# ZYNQ_BANK.net
KiCad netlist of a schematic drawn in Altium Designer
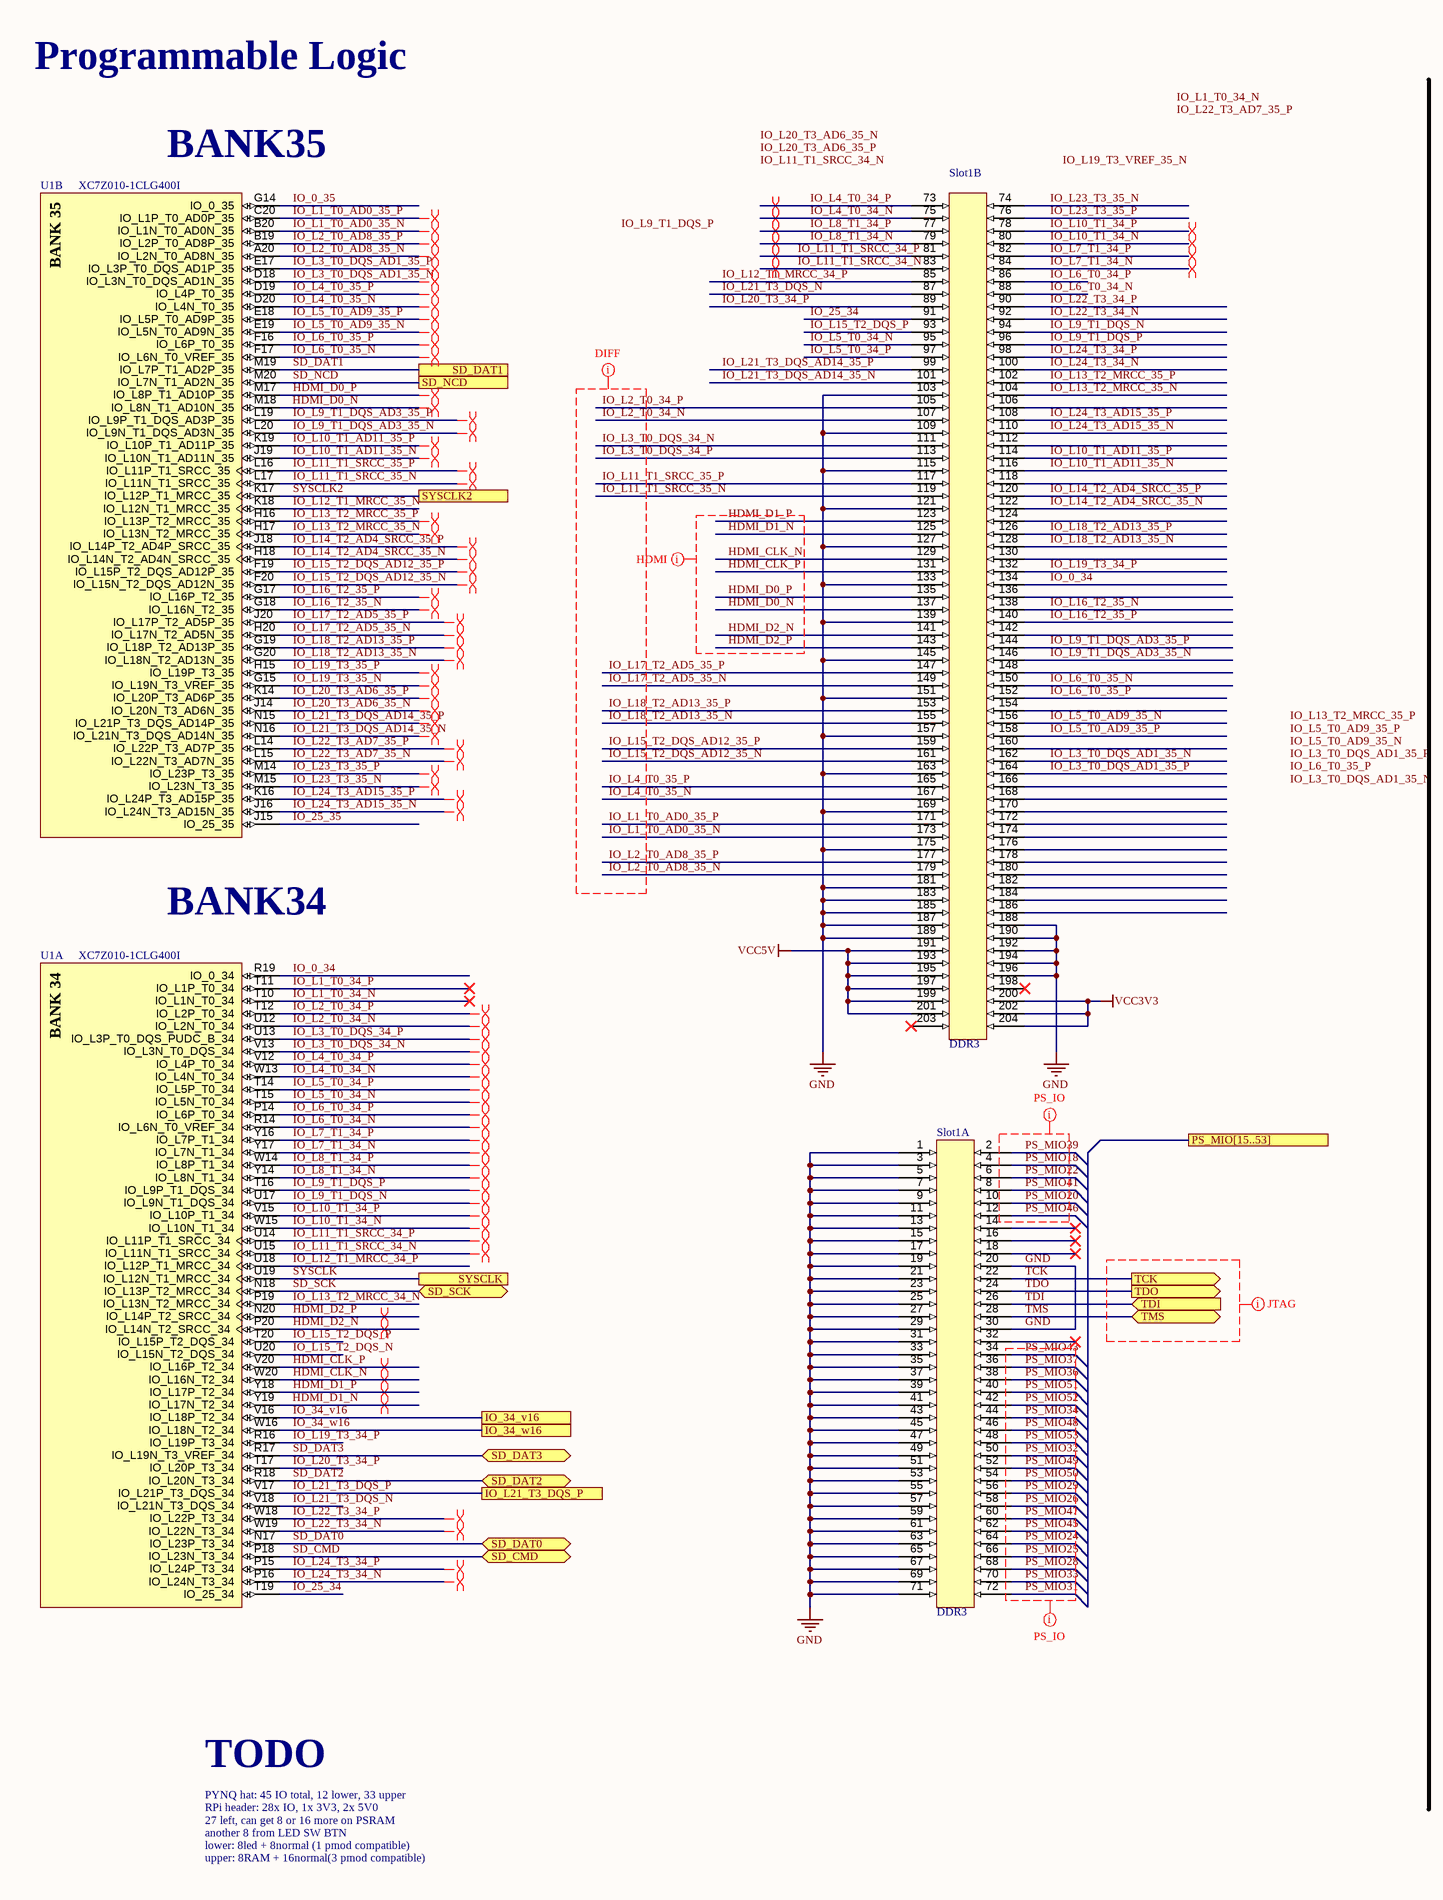
[diagram p0: ZYNQ_BANK.SchDoc, left]
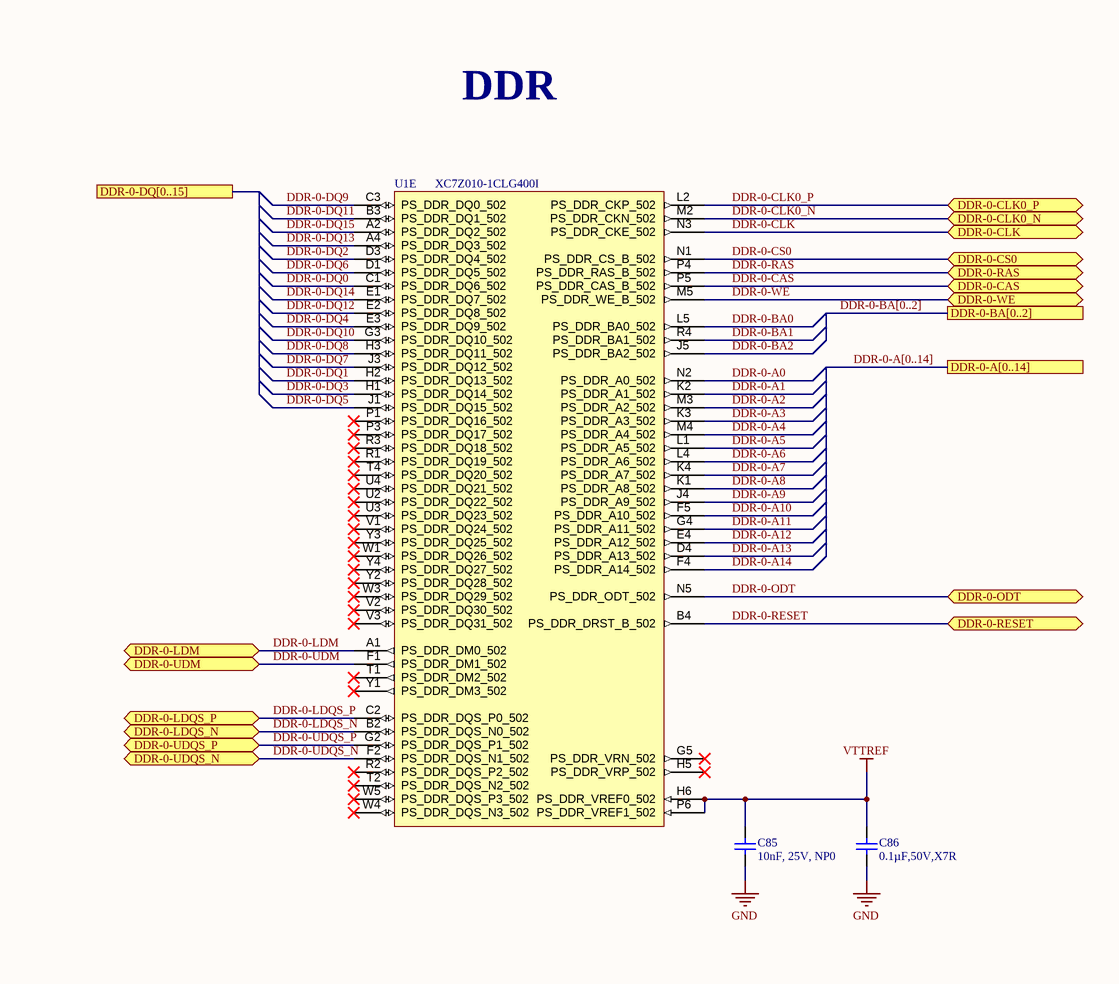
[diagram p1: ZYNQ_BANK.SchDoc, right]

(export (version "E")
  (design (tool "Eeschema 10.0.6"))
  (components
    (comp (ref "C85")
      (value "10nF, 25V, NP0")
      (footprint "CAP0402i")
      (description "0402,10nF,5%,25V,NP0")
      (fields (field (name "PART NUMBER") "GRM1555C1E103JE01J") (field (name "MANUFACTURER") "Murata"))
      (libsource (lib "AmpherLib") (part "Cap_10nF_25V_NP0_0402"))
    )
    (comp (ref "C86")
      (value "0.1µF,50V,X7R")
      (footprint "CAP0402i")
      (description "0402, 0.1uF, 10%,  50V, X7R")
      (fields (field (name "PART NUMBER") "C1005X7R1H104K050BE") (field (name "VOLTAGE") "50V"))
      (libsource (lib "AmpherLib") (part "Cap_0.1uF_50V_X7R_0402"))
    )
    (comp (ref "Slot1")
      (value "DDR3")
      (footprint "SODIMM_DDR3_EDGE")
      (libsource (lib "AmpherLib") (part "Slot_DDR3"))
    )
    (comp (ref "U1")
      (value "XC7Z010-1CLG400I")
      (footprint "CLG400")
      (fields (field (name "GENERIC PART NUMBER") "XC7Z010") (field (name "MANUFACTURER") "Xilinx"))
      (libsource (lib "CCZynq") (part "XC7Z010-1CLG400I"))
    )
  )
  (nets
    (net (code "14") (name "/DDR-0-A0") (class "Default")
      (node (ref "U1") (pin "N2") (pinfunction "PS_DDR_A0_502_N2") (pintype "output"))
    )
    (net (code "15") (name "/DDR-0-A1") (class "Default")
      (node (ref "U1") (pin "K2") (pinfunction "PS_DDR_A1_502_K2") (pintype "output"))
    )
    (net (code "16") (name "/DDR-0-A2") (class "Default")
      (node (ref "U1") (pin "M3") (pinfunction "PS_DDR_A2_502_M3") (pintype "output"))
    )
    (net (code "17") (name "/DDR-0-A3") (class "Default")
      (node (ref "U1") (pin "K3") (pinfunction "PS_DDR_A3_502_K3") (pintype "output"))
    )
    (net (code "18") (name "/DDR-0-A4") (class "Default")
      (node (ref "U1") (pin "M4") (pinfunction "PS_DDR_A4_502_M4") (pintype "output"))
    )
    (net (code "19") (name "/DDR-0-A5") (class "Default")
      (node (ref "U1") (pin "L1") (pinfunction "PS_DDR_A5_502_L1") (pintype "output"))
    )
    (net (code "20") (name "/DDR-0-A6") (class "Default")
      (node (ref "U1") (pin "L4") (pinfunction "PS_DDR_A6_502_L4") (pintype "output"))
    )
    (net (code "21") (name "/DDR-0-A7") (class "Default")
      (node (ref "U1") (pin "K4") (pinfunction "PS_DDR_A7_502_K4") (pintype "output"))
    )
    (net (code "22") (name "/DDR-0-A8") (class "Default")
      (node (ref "U1") (pin "K1") (pinfunction "PS_DDR_A8_502_K1") (pintype "output"))
    )
    (net (code "23") (name "/DDR-0-A9") (class "Default")
      (node (ref "U1") (pin "J4") (pinfunction "PS_DDR_A9_502_J4") (pintype "output"))
    )
    (net (code "24") (name "/DDR-0-A10") (class "Default")
      (node (ref "U1") (pin "F5") (pinfunction "PS_DDR_A10_502_F5") (pintype "output"))
    )
    (net (code "25") (name "/DDR-0-A11") (class "Default")
      (node (ref "U1") (pin "G4") (pinfunction "PS_DDR_A11_502_G4") (pintype "output"))
    )
    (net (code "26") (name "/DDR-0-A12") (class "Default")
      (node (ref "U1") (pin "E4") (pinfunction "PS_DDR_A12_502_E4") (pintype "output"))
    )
    (net (code "27") (name "/DDR-0-A13") (class "Default")
      (node (ref "U1") (pin "D4") (pinfunction "PS_DDR_A13_502_D4") (pintype "output"))
    )
    (net (code "28") (name "/DDR-0-A14") (class "Default")
      (node (ref "U1") (pin "F4") (pinfunction "PS_DDR_A14_502_F4") (pintype "output"))
    )
    (net (code "30") (name "/DDR-0-BA0") (class "Default")
      (node (ref "U1") (pin "L5") (pinfunction "PS_DDR_BA0_502_L5") (pintype "output"))
    )
    (net (code "31") (name "/DDR-0-BA1") (class "Default")
      (node (ref "U1") (pin "R4") (pinfunction "PS_DDR_BA1_502_R4") (pintype "output"))
    )
    (net (code "32") (name "/DDR-0-BA2") (class "Default")
      (node (ref "U1") (pin "J5") (pinfunction "PS_DDR_BA2_502_J5") (pintype "output"))
    )
    (net (code "34") (name "/DDR-0-CAS") (class "Default")
      (node (ref "U1") (pin "P5") (pinfunction "PS_DDR_CAS_B_502_P5") (pintype "output"))
    )
    (net (code "35") (name "/DDR-0-CLK") (class "Default")
      (node (ref "U1") (pin "N3") (pinfunction "PS_DDR_CKE_502_N3") (pintype "output"))
    )
    (net (code "36") (name "/DDR-0-CLK0_N") (class "Default")
      (node (ref "U1") (pin "M2") (pinfunction "PS_DDR_CKN_502_M2") (pintype "output"))
    )
    (net (code "37") (name "/DDR-0-CLK0_P") (class "Default")
      (node (ref "U1") (pin "L2") (pinfunction "PS_DDR_CKP_502_L2") (pintype "output"))
    )
    (net (code "38") (name "/DDR-0-CS0") (class "Default")
      (node (ref "U1") (pin "N1") (pinfunction "PS_DDR_CS_B_502_N1") (pintype "output"))
    )
    (net (code "39") (name "/DDR-0-DQ0") (class "Default")
      (node (ref "U1") (pin "C1") (pinfunction "PS_DDR_DQ6_502_C1") (pintype "bidirectional"))
    )
    (net (code "40") (name "/DDR-0-DQ1") (class "Default")
      (node (ref "U1") (pin "H2") (pinfunction "PS_DDR_DQ13_502_H2") (pintype "bidirectional"))
    )
    (net (code "41") (name "/DDR-0-DQ2") (class "Default")
      (node (ref "U1") (pin "D3") (pinfunction "PS_DDR_DQ4_502_D3") (pintype "bidirectional"))
    )
    (net (code "42") (name "/DDR-0-DQ3") (class "Default")
      (node (ref "U1") (pin "H1") (pinfunction "PS_DDR_DQ14_502_H1") (pintype "bidirectional"))
    )
    (net (code "43") (name "/DDR-0-DQ4") (class "Default")
      (node (ref "U1") (pin "E3") (pinfunction "PS_DDR_DQ9_502_E3") (pintype "bidirectional"))
    )
    (net (code "44") (name "/DDR-0-DQ5") (class "Default")
      (node (ref "U1") (pin "J1") (pinfunction "PS_DDR_DQ15_502_J1") (pintype "bidirectional"))
    )
    (net (code "45") (name "/DDR-0-DQ6") (class "Default")
      (node (ref "U1") (pin "D1") (pinfunction "PS_DDR_DQ5_502_D1") (pintype "bidirectional"))
    )
    (net (code "46") (name "/DDR-0-DQ7") (class "Default")
      (node (ref "U1") (pin "J3") (pinfunction "PS_DDR_DQ12_502_J3") (pintype "bidirectional"))
    )
    (net (code "47") (name "/DDR-0-DQ8") (class "Default")
      (node (ref "U1") (pin "H3") (pinfunction "PS_DDR_DQ11_502_H3") (pintype "bidirectional"))
    )
    (net (code "48") (name "/DDR-0-DQ9") (class "Default")
      (node (ref "U1") (pin "C3") (pinfunction "PS_DDR_DQ0_502_C3") (pintype "bidirectional"))
    )
    (net (code "49") (name "/DDR-0-DQ10") (class "Default")
      (node (ref "U1") (pin "G3") (pinfunction "PS_DDR_DQ10_502_G3") (pintype "bidirectional"))
    )
    (net (code "50") (name "/DDR-0-DQ11") (class "Default")
      (node (ref "U1") (pin "B3") (pinfunction "PS_DDR_DQ1_502_B3") (pintype "bidirectional"))
    )
    (net (code "51") (name "/DDR-0-DQ12") (class "Default")
      (node (ref "U1") (pin "E2") (pinfunction "PS_DDR_DQ8_502_E2") (pintype "bidirectional"))
    )
    (net (code "52") (name "/DDR-0-DQ13") (class "Default")
      (node (ref "U1") (pin "A4") (pinfunction "PS_DDR_DQ3_502_A4") (pintype "bidirectional"))
    )
    (net (code "53") (name "/DDR-0-DQ14") (class "Default")
      (node (ref "U1") (pin "E1") (pinfunction "PS_DDR_DQ7_502_E1") (pintype "bidirectional"))
    )
    (net (code "54") (name "/DDR-0-DQ15") (class "Default")
      (node (ref "U1") (pin "A2") (pinfunction "PS_DDR_DQ2_502_A2") (pintype "bidirectional"))
    )
    (net (code "56") (name "/DDR-0-LDM") (class "Default")
      (node (ref "U1") (pin "A1") (pinfunction "PS_DDR_DM0_502_A1") (pintype "output"))
    )
    (net (code "57") (name "/DDR-0-LDQS_N") (class "Default")
      (node (ref "U1") (pin "B2") (pinfunction "PS_DDR_DQS_N0_502_B2") (pintype "bidirectional"))
    )
    (net (code "58") (name "/DDR-0-LDQS_P") (class "Default")
      (node (ref "U1") (pin "C2") (pinfunction "PS_DDR_DQS_P0_502_C2") (pintype "bidirectional"))
    )
    (net (code "59") (name "/DDR-0-ODT") (class "Default")
      (node (ref "U1") (pin "N5") (pinfunction "PS_DDR_ODT_502_N5") (pintype "output"))
    )
    (net (code "60") (name "/DDR-0-RAS") (class "Default")
      (node (ref "U1") (pin "P4") (pinfunction "PS_DDR_RAS_B_502_P4") (pintype "output"))
    )
    (net (code "61") (name "/DDR-0-RESET") (class "Default")
      (node (ref "U1") (pin "B4") (pinfunction "PS_DDR_DRST_B_502_B4") (pintype "output"))
    )
    (net (code "62") (name "/DDR-0-UDM") (class "Default")
      (node (ref "U1") (pin "F1") (pinfunction "PS_DDR_DM1_502_F1") (pintype "output"))
    )
    (net (code "63") (name "/DDR-0-UDQS_N") (class "Default")
      (node (ref "U1") (pin "F2") (pinfunction "PS_DDR_DQS_N1_502_F2") (pintype "bidirectional"))
    )
    (net (code "64") (name "/DDR-0-UDQS_P") (class "Default")
      (node (ref "U1") (pin "G2") (pinfunction "PS_DDR_DQS_P1_502_G2") (pintype "bidirectional"))
    )
    (net (code "65") (name "/DDR-0-WE") (class "Default")
      (node (ref "U1") (pin "M5") (pinfunction "PS_DDR_WE_B_502_M5") (pintype "output"))
    )
    (net (code "66") (name "/HDMI_CLK_N") (class "Default")
      (node (ref "Slot1") (pin "129") (pintype "input"))
      (node (ref "U1") (pin "W20") (pinfunction "IO_L16N_T2_34_W20") (pintype "bidirectional"))
    )
    (net (code "67") (name "/HDMI_CLK_P") (class "Default")
      (node (ref "Slot1") (pin "131") (pintype "input"))
      (node (ref "U1") (pin "V20") (pinfunction "IO_L16P_T2_34_V20") (pintype "bidirectional"))
    )
    (net (code "68") (name "/HDMI_D0_N") (class "Default")
      (node (ref "Slot1") (pin "137") (pintype "input"))
      (node (ref "U1") (pin "M18") (pinfunction "IO_L8N_T1_AD10N_35_M18") (pintype "bidirectional"))
    )
    (net (code "69") (name "/HDMI_D0_P") (class "Default")
      (node (ref "Slot1") (pin "135") (pintype "input"))
      (node (ref "U1") (pin "M17") (pinfunction "IO_L8P_T1_AD10P_35_M17") (pintype "bidirectional"))
    )
    (net (code "70") (name "/HDMI_D1_N") (class "Default")
      (node (ref "Slot1") (pin "125") (pintype "input"))
      (node (ref "U1") (pin "Y19") (pinfunction "IO_L17N_T2_34_Y19") (pintype "bidirectional"))
    )
    (net (code "71") (name "/HDMI_D1_P") (class "Default")
      (node (ref "Slot1") (pin "123") (pintype "input"))
      (node (ref "U1") (pin "Y18") (pinfunction "IO_L17P_T2_34_Y18") (pintype "bidirectional"))
    )
    (net (code "72") (name "/HDMI_D2_N") (class "Default")
      (node (ref "Slot1") (pin "141") (pintype "input"))
      (node (ref "U1") (pin "P20") (pinfunction "IO_L14N_T2_SRCC_34_P20") (pintype "bidirectional"))
    )
    (net (code "73") (name "/HDMI_D2_P") (class "Default")
      (node (ref "Slot1") (pin "143") (pintype "input"))
      (node (ref "U1") (pin "N20") (pinfunction "IO_L14P_T2_SRCC_34_N20") (pintype "bidirectional"))
    )
    (net (code "74") (name "/IO_0_34") (class "Default")
      (node (ref "Slot1") (pin "134") (pintype "input"))
      (node (ref "U1") (pin "R19") (pinfunction "IO_0_34_R19") (pintype "bidirectional"))
    )
    (net (code "75") (name "/IO_0_35") (class "Default")
      (node (ref "U1") (pin "G14") (pinfunction "IO_0_35_G14") (pintype "bidirectional"))
    )
    (net (code "76") (name "/IO_25_34") (class "Default")
      (node (ref "Slot1") (pin "91") (pintype "input"))
      (node (ref "U1") (pin "T19") (pinfunction "IO_25_34_T19") (pintype "bidirectional"))
    )
    (net (code "77") (name "/IO_25_35") (class "Default")
      (node (ref "U1") (pin "J15") (pinfunction "IO_25_35_J15") (pintype "bidirectional"))
    )
    (net (code "78") (name "/IO_34_v16") (class "Default")
      (node (ref "U1") (pin "V16") (pinfunction "IO_L18P_T2_34_V16") (pintype "bidirectional"))
    )
    (net (code "79") (name "/IO_34_w16") (class "Default")
      (node (ref "U1") (pin "W16") (pinfunction "IO_L18N_T2_34_W16") (pintype "bidirectional"))
    )
    (net (code "80") (name "/IO_L1_T0_34_N") (class "Default")
      (node (ref "U1") (pin "T10") (pinfunction "IO_L1N_T0_34_T10") (pintype "bidirectional+no_connect"))
    )
    (net (code "81") (name "/IO_L1_T0_34_P") (class "Default")
      (node (ref "U1") (pin "T11") (pinfunction "IO_L1P_T0_34_T11") (pintype "bidirectional+no_connect"))
    )
    (net (code "82") (name "/IO_L1_T0_AD0_35_N") (class "Default")
      (node (ref "Slot1") (pin "173") (pintype "input"))
      (node (ref "U1") (pin "B20") (pinfunction "IO_L1N_T0_AD0N_35_B20") (pintype "bidirectional"))
    )
    (net (code "83") (name "/IO_L1_T0_AD0_35_P") (class "Default")
      (node (ref "Slot1") (pin "171") (pintype "input"))
      (node (ref "U1") (pin "C20") (pinfunction "IO_L1P_T0_AD0P_35_C20") (pintype "bidirectional"))
    )
    (net (code "84") (name "/IO_L2_T0_34_N") (class "Default")
      (node (ref "Slot1") (pin "107") (pintype "input"))
      (node (ref "U1") (pin "U12") (pinfunction "IO_L2N_T0_34_U12") (pintype "bidirectional"))
    )
    (net (code "85") (name "/IO_L2_T0_34_P") (class "Default")
      (node (ref "Slot1") (pin "105") (pintype "input"))
      (node (ref "U1") (pin "T12") (pinfunction "IO_L2P_T0_34_T12") (pintype "bidirectional"))
    )
    (net (code "86") (name "/IO_L2_T0_AD8_35_N") (class "Default")
      (node (ref "Slot1") (pin "179") (pintype "input"))
      (node (ref "U1") (pin "A20") (pinfunction "IO_L2N_T0_AD8N_35_A20") (pintype "bidirectional"))
    )
    (net (code "87") (name "/IO_L2_T0_AD8_35_P") (class "Default")
      (node (ref "Slot1") (pin "177") (pintype "input"))
      (node (ref "U1") (pin "B19") (pinfunction "IO_L2P_T0_AD8P_35_B19") (pintype "bidirectional"))
    )
    (net (code "88") (name "/IO_L3_T0_DQS_34_N") (class "Default")
      (node (ref "Slot1") (pin "111") (pintype "input"))
      (node (ref "U1") (pin "V13") (pinfunction "IO_L3N_T0_DQS_34_V13") (pintype "bidirectional"))
    )
    (net (code "89") (name "/IO_L3_T0_DQS_34_P") (class "Default")
      (node (ref "Slot1") (pin "113") (pintype "input"))
      (node (ref "U1") (pin "U13") (pinfunction "IO_L3P_T0_DQS_PUDC_B_34_U13") (pintype "bidirectional"))
    )
    (net (code "90") (name "/IO_L3_T0_DQS_AD1_35_N") (class "Default")
      (node (ref "Slot1") (pin "162") (pintype "input"))
      (node (ref "U1") (pin "D18") (pinfunction "IO_L3N_T0_DQS_AD1N_35_D18") (pintype "bidirectional"))
    )
    (net (code "91") (name "/IO_L3_T0_DQS_AD1_35_P") (class "Default")
      (node (ref "Slot1") (pin "164") (pintype "input"))
      (node (ref "U1") (pin "E17") (pinfunction "IO_L3P_T0_DQS_AD1P_35_E17") (pintype "bidirectional"))
    )
    (net (code "92") (name "/IO_L4_T0_34_N") (class "Default")
      (node (ref "Slot1") (pin "75") (pintype "input"))
      (node (ref "U1") (pin "W13") (pinfunction "IO_L4N_T0_34_W13") (pintype "bidirectional"))
    )
    (net (code "93") (name "/IO_L4_T0_34_P") (class "Default")
      (node (ref "Slot1") (pin "73") (pintype "input"))
      (node (ref "U1") (pin "V12") (pinfunction "IO_L4P_T0_34_V12") (pintype "bidirectional"))
    )
    (net (code "94") (name "/IO_L4_T0_35_N") (class "Default")
      (node (ref "Slot1") (pin "167") (pintype "input"))
      (node (ref "U1") (pin "D20") (pinfunction "IO_L4N_T0_35_D20") (pintype "bidirectional"))
    )
    (net (code "95") (name "/IO_L4_T0_35_P") (class "Default")
      (node (ref "Slot1") (pin "165") (pintype "input"))
      (node (ref "U1") (pin "D19") (pinfunction "IO_L4P_T0_35_D19") (pintype "bidirectional"))
    )
    (net (code "96") (name "/IO_L5_T0_34_N") (class "Default")
      (node (ref "Slot1") (pin "95") (pintype "input"))
      (node (ref "U1") (pin "T15") (pinfunction "IO_L5N_T0_34_T15") (pintype "bidirectional"))
    )
    (net (code "97") (name "/IO_L5_T0_34_P") (class "Default")
      (node (ref "Slot1") (pin "97") (pintype "input"))
      (node (ref "U1") (pin "T14") (pinfunction "IO_L5P_T0_34_T14") (pintype "bidirectional"))
    )
    (net (code "98") (name "/IO_L5_T0_AD9_35_N") (class "Default")
      (node (ref "Slot1") (pin "156") (pintype "input"))
      (node (ref "U1") (pin "E19") (pinfunction "IO_L5N_T0_AD9N_35_E19") (pintype "bidirectional"))
    )
    (net (code "99") (name "/IO_L5_T0_AD9_35_P") (class "Default")
      (node (ref "Slot1") (pin "158") (pintype "input"))
      (node (ref "U1") (pin "E18") (pinfunction "IO_L5P_T0_AD9P_35_E18") (pintype "bidirectional"))
    )
    (net (code "100") (name "/IO_L6_T0_34_N") (class "Default")
      (node (ref "Slot1") (pin "88") (pintype "input"))
      (node (ref "U1") (pin "R14") (pinfunction "IO_L6N_T0_VREF_34_R14") (pintype "bidirectional"))
    )
    (net (code "101") (name "/IO_L6_T0_34_P") (class "Default")
      (node (ref "Slot1") (pin "86") (pintype "input"))
      (node (ref "U1") (pin "P14") (pinfunction "IO_L6P_T0_34_P14") (pintype "bidirectional"))
    )
    (net (code "102") (name "/IO_L6_T0_35_N") (class "Default")
      (node (ref "Slot1") (pin "150") (pintype "input"))
      (node (ref "U1") (pin "F17") (pinfunction "IO_L6N_T0_VREF_35_F17") (pintype "bidirectional"))
    )
    (net (code "103") (name "/IO_L6_T0_35_P") (class "Default")
      (node (ref "Slot1") (pin "152") (pintype "input"))
      (node (ref "U1") (pin "F16") (pinfunction "IO_L6P_T0_35_F16") (pintype "bidirectional"))
    )
    (net (code "104") (name "/IO_L7_T1_34_N") (class "Default")
      (node (ref "Slot1") (pin "84") (pintype "input"))
      (node (ref "U1") (pin "Y17") (pinfunction "IO_L7N_T1_34_Y17") (pintype "bidirectional"))
    )
    (net (code "105") (name "/IO_L7_T1_34_P") (class "Default")
      (node (ref "Slot1") (pin "82") (pintype "input"))
      (node (ref "U1") (pin "Y16") (pinfunction "IO_L7P_T1_34_Y16") (pintype "bidirectional"))
    )
    (net (code "106") (name "/IO_L8_T1_34_N") (class "Default")
      (node (ref "Slot1") (pin "79") (pintype "input"))
      (node (ref "U1") (pin "Y14") (pinfunction "IO_L8N_T1_34_Y14") (pintype "bidirectional"))
    )
    (net (code "107") (name "/IO_L8_T1_34_P") (class "Default")
      (node (ref "Slot1") (pin "77") (pintype "input"))
      (node (ref "U1") (pin "W14") (pinfunction "IO_L8P_T1_34_W14") (pintype "bidirectional"))
    )
    (net (code "108") (name "/IO_L9_T1_DQS_AD3_35_N") (class "Default")
      (node (ref "Slot1") (pin "146") (pintype "input"))
      (node (ref "U1") (pin "L20") (pinfunction "IO_L9N_T1_DQS_AD3N_35_L20") (pintype "bidirectional"))
    )
    (net (code "109") (name "/IO_L9_T1_DQS_AD3_35_P") (class "Default")
      (node (ref "Slot1") (pin "144") (pintype "input"))
      (node (ref "U1") (pin "L19") (pinfunction "IO_L9P_T1_DQS_AD3P_35_L19") (pintype "bidirectional"))
    )
    (net (code "110") (name "/IO_L9_T1_DQS_N") (class "Default")
      (node (ref "Slot1") (pin "94") (pintype "input"))
      (node (ref "U1") (pin "U17") (pinfunction "IO_L9N_T1_DQS_34_U17") (pintype "bidirectional"))
    )
    (net (code "111") (name "/IO_L9_T1_DQS_P") (class "Default")
      (node (ref "Slot1") (pin "96") (pintype "input"))
      (node (ref "U1") (pin "T16") (pinfunction "IO_L9P_T1_DQS_34_T16") (pintype "bidirectional"))
    )
    (net (code "112") (name "/IO_L10_T1_34_N") (class "Default")
      (node (ref "Slot1") (pin "80") (pintype "input"))
      (node (ref "U1") (pin "W15") (pinfunction "IO_L10N_T1_34_W15") (pintype "bidirectional"))
    )
    (net (code "113") (name "/IO_L10_T1_34_P") (class "Default")
      (node (ref "Slot1") (pin "78") (pintype "input"))
      (node (ref "U1") (pin "V15") (pinfunction "IO_L10P_T1_34_V15") (pintype "bidirectional"))
    )
    (net (code "114") (name "/IO_L10_T1_AD11_35_N") (class "Default")
      (node (ref "Slot1") (pin "116") (pintype "input"))
      (node (ref "U1") (pin "J19") (pinfunction "IO_L10N_T1_AD11N_35_J19") (pintype "bidirectional"))
    )
    (net (code "115") (name "/IO_L10_T1_AD11_35_P") (class "Default")
      (node (ref "Slot1") (pin "114") (pintype "input"))
      (node (ref "U1") (pin "K19") (pinfunction "IO_L10P_T1_AD11P_35_K19") (pintype "bidirectional"))
    )
    (net (code "116") (name "/IO_L11_T1_SRCC_34_N") (class "Default")
      (node (ref "Slot1") (pin "83") (pintype "input"))
      (node (ref "U1") (pin "U15") (pinfunction "IO_L11N_T1_SRCC_34_U15") (pintype "bidirectional"))
    )
    (net (code "117") (name "/IO_L11_T1_SRCC_34_P") (class "Default")
      (node (ref "Slot1") (pin "81") (pintype "input"))
      (node (ref "U1") (pin "U14") (pinfunction "IO_L11P_T1_SRCC_34_U14") (pintype "bidirectional"))
    )
    (net (code "118") (name "/IO_L11_T1_SRCC_35_N") (class "Default")
      (node (ref "Slot1") (pin "119") (pintype "input"))
      (node (ref "U1") (pin "L17") (pinfunction "IO_L11N_T1_SRCC_35_L17") (pintype "bidirectional"))
    )
    (net (code "119") (name "/IO_L11_T1_SRCC_35_P") (class "Default")
      (node (ref "Slot1") (pin "117") (pintype "input"))
      (node (ref "U1") (pin "L16") (pinfunction "IO_L11P_T1_SRCC_35_L16") (pintype "bidirectional"))
    )
    (net (code "120") (name "/IO_L12_T1_MRCC_34_P") (class "Default")
      (node (ref "Slot1") (pin "85") (pintype "input"))
      (node (ref "U1") (pin "U18") (pinfunction "IO_L12P_T1_MRCC_34_U18") (pintype "bidirectional"))
    )
    (net (code "121") (name "/IO_L12_T1_MRCC_35_N") (class "Default")
      (node (ref "U1") (pin "K18") (pinfunction "IO_L12N_T1_MRCC_35_K18") (pintype "bidirectional"))
    )
    (net (code "122") (name "/IO_L13_T2_MRCC_34_N") (class "Default")
      (node (ref "U1") (pin "P19") (pinfunction "IO_L13N_T2_MRCC_34_P19") (pintype "bidirectional"))
    )
    (net (code "123") (name "/IO_L13_T2_MRCC_35_N") (class "Default")
      (node (ref "Slot1") (pin "104") (pintype "input"))
      (node (ref "U1") (pin "H17") (pinfunction "IO_L13N_T2_MRCC_35_H17") (pintype "bidirectional"))
    )
    (net (code "124") (name "/IO_L13_T2_MRCC_35_P") (class "Default")
      (node (ref "Slot1") (pin "102") (pintype "input"))
      (node (ref "U1") (pin "H16") (pinfunction "IO_L13P_T2_MRCC_35_H16") (pintype "bidirectional"))
    )
    (net (code "125") (name "/IO_L14_T2_AD4_SRCC_35_N") (class "Default")
      (node (ref "Slot1") (pin "122") (pintype "input"))
      (node (ref "U1") (pin "H18") (pinfunction "IO_L14N_T2_AD4N_SRCC_35_H18") (pintype "bidirectional"))
    )
    (net (code "126") (name "/IO_L14_T2_AD4_SRCC_35_P") (class "Default")
      (node (ref "Slot1") (pin "120") (pintype "input"))
      (node (ref "U1") (pin "J18") (pinfunction "IO_L14P_T2_AD4P_SRCC_35_J18") (pintype "bidirectional"))
    )
    (net (code "127") (name "/IO_L15_T2_DQS_AD12_35_N") (class "Default")
      (node (ref "Slot1") (pin "161") (pintype "input"))
      (node (ref "U1") (pin "F20") (pinfunction "IO_L15N_T2_DQS_AD12N_35_F20") (pintype "bidirectional"))
    )
    (net (code "128") (name "/IO_L15_T2_DQS_AD12_35_P") (class "Default")
      (node (ref "Slot1") (pin "159") (pintype "input"))
      (node (ref "U1") (pin "F19") (pinfunction "IO_L15P_T2_DQS_AD12P_35_F19") (pintype "bidirectional"))
    )
    (net (code "129") (name "/IO_L15_T2_DQS_N") (class "Default")
      (node (ref "U1") (pin "U20") (pinfunction "IO_L15N_T2_DQS_34_U20") (pintype "bidirectional"))
    )
    (net (code "130") (name "/IO_L15_T2_DQS_P") (class "Default")
      (node (ref "Slot1") (pin "93") (pintype "input"))
      (node (ref "U1") (pin "T20") (pinfunction "IO_L15P_T2_DQS_34_T20") (pintype "bidirectional"))
    )
    (net (code "131") (name "/IO_L16_T2_35_N") (class "Default")
      (node (ref "Slot1") (pin "138") (pintype "input"))
      (node (ref "U1") (pin "G18") (pinfunction "IO_L16N_T2_35_G18") (pintype "bidirectional"))
    )
    (net (code "132") (name "/IO_L16_T2_35_P") (class "Default")
      (node (ref "Slot1") (pin "140") (pintype "input"))
      (node (ref "U1") (pin "G17") (pinfunction "IO_L16P_T2_35_G17") (pintype "bidirectional"))
    )
    (net (code "133") (name "/IO_L17_T2_AD5_35_N") (class "Default")
      (node (ref "Slot1") (pin "149") (pintype "input"))
      (node (ref "U1") (pin "H20") (pinfunction "IO_L17N_T2_AD5N_35_H20") (pintype "bidirectional"))
    )
    (net (code "134") (name "/IO_L17_T2_AD5_35_P") (class "Default")
      (node (ref "Slot1") (pin "147") (pintype "input"))
      (node (ref "U1") (pin "J20") (pinfunction "IO_L17P_T2_AD5P_35_J20") (pintype "bidirectional"))
    )
    (net (code "135") (name "/IO_L18_T2_AD13_35_N") (class "Default")
      (node (ref "Slot1") (pin "128") (pintype "input"))
      (node (ref "Slot1") (pin "155") (pintype "input"))
      (node (ref "U1") (pin "G20") (pinfunction "IO_L18N_T2_AD13N_35_G20") (pintype "bidirectional"))
    )
    (net (code "136") (name "/IO_L18_T2_AD13_35_P") (class "Default")
      (node (ref "Slot1") (pin "126") (pintype "input"))
      (node (ref "Slot1") (pin "153") (pintype "input"))
      (node (ref "U1") (pin "G19") (pinfunction "IO_L18P_T2_AD13P_35_G19") (pintype "bidirectional"))
    )
    (net (code "137") (name "/IO_L19_T3_34_P") (class "Default")
      (node (ref "Slot1") (pin "132") (pintype "input"))
      (node (ref "U1") (pin "R16") (pinfunction "IO_L19P_T3_34_R16") (pintype "bidirectional"))
    )
    (net (code "138") (name "/IO_L19_T3_35_N") (class "Default")
      (node (ref "U1") (pin "G15") (pinfunction "IO_L19N_T3_VREF_35_G15") (pintype "bidirectional"))
    )
    (net (code "139") (name "/IO_L19_T3_35_P") (class "Default")
      (node (ref "U1") (pin "H15") (pinfunction "IO_L19P_T3_35_H15") (pintype "bidirectional"))
    )
    (net (code "141") (name "/IO_L20_T3_34_P") (class "Default")
      (node (ref "Slot1") (pin "89") (pintype "input"))
      (node (ref "U1") (pin "T17") (pinfunction "IO_L20P_T3_34_T17") (pintype "bidirectional"))
    )
    (net (code "142") (name "/IO_L20_T3_AD6_35_N") (class "Default")
      (node (ref "U1") (pin "J14") (pinfunction "IO_L20N_T3_AD6N_35_J14") (pintype "bidirectional"))
    )
    (net (code "143") (name "/IO_L20_T3_AD6_35_P") (class "Default")
      (node (ref "U1") (pin "K14") (pinfunction "IO_L20P_T3_AD6P_35_K14") (pintype "bidirectional"))
    )
    (net (code "144") (name "/IO_L21_T3_DQS_AD14_35_N") (class "Default")
      (node (ref "Slot1") (pin "101") (pintype "input"))
      (node (ref "U1") (pin "N16") (pinfunction "IO_L21N_T3_DQS_AD14N_35_N16") (pintype "bidirectional"))
    )
    (net (code "145") (name "/IO_L21_T3_DQS_AD14_35_P") (class "Default")
      (node (ref "Slot1") (pin "99") (pintype "input"))
      (node (ref "U1") (pin "N15") (pinfunction "IO_L21P_T3_DQS_AD14P_35_N15") (pintype "bidirectional"))
    )
    (net (code "146") (name "/IO_L21_T3_DQS_N") (class "Default")
      (node (ref "Slot1") (pin "87") (pintype "input"))
      (node (ref "U1") (pin "V18") (pinfunction "IO_L21N_T3_DQS_34_V18") (pintype "bidirectional"))
    )
    (net (code "147") (name "/IO_L21_T3_DQS_P") (class "Default")
      (node (ref "U1") (pin "V17") (pinfunction "IO_L21P_T3_DQS_34_V17") (pintype "bidirectional"))
    )
    (net (code "148") (name "/IO_L22_T3_34_N") (class "Default")
      (node (ref "Slot1") (pin "92") (pintype "input"))
      (node (ref "U1") (pin "W19") (pinfunction "IO_L22N_T3_34_W19") (pintype "bidirectional"))
    )
    (net (code "149") (name "/IO_L22_T3_34_P") (class "Default")
      (node (ref "Slot1") (pin "90") (pintype "input"))
      (node (ref "U1") (pin "W18") (pinfunction "IO_L22P_T3_34_W18") (pintype "bidirectional"))
    )
    (net (code "150") (name "/IO_L22_T3_AD7_35_N") (class "Default")
      (node (ref "U1") (pin "L15") (pinfunction "IO_L22N_T3_AD7N_35_L15") (pintype "bidirectional"))
    )
    (net (code "151") (name "/IO_L22_T3_AD7_35_P") (class "Default")
      (node (ref "U1") (pin "L14") (pinfunction "IO_L22P_T3_AD7P_35_L14") (pintype "bidirectional"))
    )
    (net (code "152") (name "/IO_L23_T3_35_N") (class "Default")
      (node (ref "Slot1") (pin "74") (pintype "input"))
      (node (ref "U1") (pin "M15") (pinfunction "IO_L23N_T3_35_M15") (pintype "bidirectional"))
    )
    (net (code "153") (name "/IO_L23_T3_35_P") (class "Default")
      (node (ref "Slot1") (pin "76") (pintype "input"))
      (node (ref "U1") (pin "M14") (pinfunction "IO_L23P_T3_35_M14") (pintype "bidirectional"))
    )
    (net (code "154") (name "/IO_L24_T3_34_N") (class "Default")
      (node (ref "Slot1") (pin "100") (pintype "input"))
      (node (ref "U1") (pin "P16") (pinfunction "IO_L24N_T3_34_P16") (pintype "bidirectional"))
    )
    (net (code "155") (name "/IO_L24_T3_34_P") (class "Default")
      (node (ref "Slot1") (pin "98") (pintype "input"))
      (node (ref "U1") (pin "P15") (pinfunction "IO_L24P_T3_34_P15") (pintype "bidirectional"))
    )
    (net (code "156") (name "/IO_L24_T3_AD15_35_N") (class "Default")
      (node (ref "Slot1") (pin "110") (pintype "input"))
      (node (ref "U1") (pin "J16") (pinfunction "IO_L24N_T3_AD15N_35_J16") (pintype "bidirectional"))
    )
    (net (code "157") (name "/IO_L24_T3_AD15_35_P") (class "Default")
      (node (ref "Slot1") (pin "108") (pintype "input"))
      (node (ref "U1") (pin "K16") (pinfunction "IO_L24P_T3_AD15P_35_K16") (pintype "bidirectional"))
    )
    (net (code "158") (name "/PS_MIO18") (class "Default") (node (ref "Slot1") (pin "4") (pintype "input")))
    (net (code "159") (name "/PS_MIO20") (class "Default") (node (ref "Slot1") (pin "10") (pintype "input")))
    (net (code "160") (name "/PS_MIO22") (class "Default") (node (ref "Slot1") (pin "6") (pintype "input")))
    (net (code "161") (name "/PS_MIO24") (class "Default") (node (ref "Slot1") (pin "64") (pintype "input")))
    (net (code "162") (name "/PS_MIO25") (class "Default") (node (ref "Slot1") (pin "66") (pintype "input")))
    (net (code "163") (name "/PS_MIO26") (class "Default") (node (ref "Slot1") (pin "58") (pintype "input")))
    (net (code "164") (name "/PS_MIO28") (class "Default") (node (ref "Slot1") (pin "68") (pintype "input")))
    (net (code "165") (name "/PS_MIO29") (class "Default") (node (ref "Slot1") (pin "56") (pintype "input")))
    (net (code "166") (name "/PS_MIO31") (class "Default") (node (ref "Slot1") (pin "72") (pintype "input")))
    (net (code "167") (name "/PS_MIO32") (class "Default") (node (ref "Slot1") (pin "50") (pintype "input")))
    (net (code "168") (name "/PS_MIO33") (class "Default") (node (ref "Slot1") (pin "70") (pintype "input")))
    (net (code "169") (name "/PS_MIO34") (class "Default") (node (ref "Slot1") (pin "44") (pintype "input")))
    (net (code "170") (name "/PS_MIO36") (class "Default") (node (ref "Slot1") (pin "38") (pintype "input")))
    (net (code "171") (name "/PS_MIO37") (class "Default") (node (ref "Slot1") (pin "36") (pintype "input")))
    (net (code "172") (name "/PS_MIO39") (class "Default") (node (ref "Slot1") (pin "2") (pintype "input")))
    (net (code "173") (name "/PS_MIO41") (class "Default") (node (ref "Slot1") (pin "8") (pintype "input")))
    (net (code "174") (name "/PS_MIO43") (class "Default") (node (ref "Slot1") (pin "34") (pintype "input")))
    (net (code "175") (name "/PS_MIO45") (class "Default") (node (ref "Slot1") (pin "62") (pintype "input")))
    (net (code "176") (name "/PS_MIO46") (class "Default") (node (ref "Slot1") (pin "12") (pintype "input")))
    (net (code "177") (name "/PS_MIO47") (class "Default") (node (ref "Slot1") (pin "60") (pintype "input")))
    (net (code "178") (name "/PS_MIO48") (class "Default") (node (ref "Slot1") (pin "46") (pintype "input")))
    (net (code "179") (name "/PS_MIO49") (class "Default") (node (ref "Slot1") (pin "52") (pintype "input")))
    (net (code "180") (name "/PS_MIO50") (class "Default") (node (ref "Slot1") (pin "54") (pintype "input")))
    (net (code "181") (name "/PS_MIO51") (class "Default") (node (ref "Slot1") (pin "40") (pintype "input")))
    (net (code "182") (name "/PS_MIO52") (class "Default") (node (ref "Slot1") (pin "42") (pintype "input")))
    (net (code "183") (name "/PS_MIO53") (class "Default") (node (ref "Slot1") (pin "48") (pintype "input")))
    (net (code "185") (name "/SD_CMD") (class "Default")
      (node (ref "U1") (pin "P18") (pinfunction "IO_L23N_T3_34_P18") (pintype "bidirectional"))
    )
    (net (code "186") (name "/SD_DAT0") (class "Default")
      (node (ref "U1") (pin "N17") (pinfunction "IO_L23P_T3_34_N17") (pintype "bidirectional"))
    )
    (net (code "187") (name "/SD_DAT1") (class "Default")
      (node (ref "U1") (pin "M19") (pinfunction "IO_L7P_T1_AD2P_35_M19") (pintype "bidirectional"))
    )
    (net (code "188") (name "/SD_DAT2") (class "Default")
      (node (ref "U1") (pin "R18") (pinfunction "IO_L20N_T3_34_R18") (pintype "bidirectional"))
    )
    (net (code "189") (name "/SD_DAT3") (class "Default")
      (node (ref "U1") (pin "R17") (pinfunction "IO_L19N_T3_VREF_34_R17") (pintype "bidirectional"))
    )
    (net (code "190") (name "/SD_NCD") (class "Default")
      (node (ref "U1") (pin "M20") (pinfunction "IO_L7N_T1_AD2N_35_M20") (pintype "bidirectional"))
    )
    (net (code "191") (name "/SD_SCK") (class "Default")
      (node (ref "U1") (pin "N18") (pinfunction "IO_L13P_T2_MRCC_34_N18") (pintype "bidirectional"))
    )
    (net (code "192") (name "/SYSCLK") (class "Default")
      (node (ref "U1") (pin "U19") (pinfunction "IO_L12N_T1_MRCC_34_U19") (pintype "bidirectional"))
    )
    (net (code "193") (name "/SYSCLK2") (class "Default")
      (node (ref "U1") (pin "K17") (pinfunction "IO_L12P_T1_MRCC_35_K17") (pintype "bidirectional"))
    )
    (net (code "194") (name "/TCK") (class "Default") (node (ref "Slot1") (pin "22") (pintype "input")))
    (net (code "195") (name "/TDI") (class "Default") (node (ref "Slot1") (pin "26") (pintype "input")))
    (net (code "196") (name "/TDO") (class "Default") (node (ref "Slot1") (pin "24") (pintype "input")))
    (net (code "197") (name "/TMS") (class "Default") (node (ref "Slot1") (pin "28") (pintype "input")))
    (net (code "198") (name "GND") (class "Default")
      (node (ref "C85") (pin "1") (pinfunction "1_1") (pintype "passive"))
      (node (ref "C86") (pin "1") (pinfunction "1_1") (pintype "passive"))
      (node (ref "Slot1") (pin "1") (pintype "input"))
      (node (ref "Slot1") (pin "103") (pintype "input"))
      (node (ref "Slot1") (pin "109") (pintype "input"))
      (node (ref "Slot1") (pin "11") (pintype "input"))
      (node (ref "Slot1") (pin "115") (pintype "input"))
      (node (ref "Slot1") (pin "121") (pintype "input"))
      (node (ref "Slot1") (pin "127") (pintype "input"))
      (node (ref "Slot1") (pin "13") (pintype "input"))
      (node (ref "Slot1") (pin "133") (pintype "input"))
      (node (ref "Slot1") (pin "139") (pintype "input"))
      (node (ref "Slot1") (pin "145") (pintype "input"))
      (node (ref "Slot1") (pin "15") (pintype "input"))
      (node (ref "Slot1") (pin "151") (pintype "input"))
      (node (ref "Slot1") (pin "157") (pintype "input"))
      (node (ref "Slot1") (pin "163") (pintype "input"))
      (node (ref "Slot1") (pin "169") (pintype "input"))
      (node (ref "Slot1") (pin "17") (pintype "input"))
      (node (ref "Slot1") (pin "175") (pintype "input"))
      (node (ref "Slot1") (pin "181") (pintype "input"))
      (node (ref "Slot1") (pin "183") (pintype "input"))
      (node (ref "Slot1") (pin "185") (pintype "input"))
      (node (ref "Slot1") (pin "187") (pintype "input"))
      (node (ref "Slot1") (pin "188") (pintype "input"))
      (node (ref "Slot1") (pin "189") (pintype "input"))
      (node (ref "Slot1") (pin "19") (pintype "input"))
      (node (ref "Slot1") (pin "190") (pintype "input"))
      (node (ref "Slot1") (pin "192") (pintype "input"))
      (node (ref "Slot1") (pin "194") (pintype "input"))
      (node (ref "Slot1") (pin "196") (pintype "input"))
      (node (ref "Slot1") (pin "20") (pintype "input"))
      (node (ref "Slot1") (pin "21") (pintype "input"))
      (node (ref "Slot1") (pin "23") (pintype "input"))
      (node (ref "Slot1") (pin "25") (pintype "input"))
      (node (ref "Slot1") (pin "27") (pintype "input"))
      (node (ref "Slot1") (pin "29") (pintype "input"))
      (node (ref "Slot1") (pin "3") (pintype "input"))
      (node (ref "Slot1") (pin "30") (pintype "input"))
      (node (ref "Slot1") (pin "31") (pintype "input"))
      (node (ref "Slot1") (pin "33") (pintype "input"))
      (node (ref "Slot1") (pin "35") (pintype "input"))
      (node (ref "Slot1") (pin "37") (pintype "input"))
      (node (ref "Slot1") (pin "39") (pintype "input"))
      (node (ref "Slot1") (pin "41") (pintype "input"))
      (node (ref "Slot1") (pin "43") (pintype "input"))
      (node (ref "Slot1") (pin "45") (pintype "input"))
      (node (ref "Slot1") (pin "47") (pintype "input"))
      (node (ref "Slot1") (pin "49") (pintype "input"))
      (node (ref "Slot1") (pin "5") (pintype "input"))
      (node (ref "Slot1") (pin "51") (pintype "input"))
      (node (ref "Slot1") (pin "53") (pintype "input"))
      (node (ref "Slot1") (pin "55") (pintype "input"))
      (node (ref "Slot1") (pin "57") (pintype "input"))
      (node (ref "Slot1") (pin "59") (pintype "input"))
      (node (ref "Slot1") (pin "61") (pintype "input"))
      (node (ref "Slot1") (pin "63") (pintype "input"))
      (node (ref "Slot1") (pin "65") (pintype "input"))
      (node (ref "Slot1") (pin "67") (pintype "input"))
      (node (ref "Slot1") (pin "69") (pintype "input"))
      (node (ref "Slot1") (pin "7") (pintype "input"))
      (node (ref "Slot1") (pin "71") (pintype "input"))
      (node (ref "Slot1") (pin "9") (pintype "input"))
    )
    (net (code "199") (name "VCC3V3") (class "Default")
      (node (ref "Slot1") (pin "200") (pintype "input"))
      (node (ref "Slot1") (pin "202") (pintype "input"))
      (node (ref "Slot1") (pin "204") (pintype "input"))
    )
    (net (code "200") (name "VCC5V") (class "Default")
      (node (ref "Slot1") (pin "191") (pintype "input"))
      (node (ref "Slot1") (pin "193") (pintype "input"))
      (node (ref "Slot1") (pin "195") (pintype "input"))
      (node (ref "Slot1") (pin "197") (pintype "input"))
      (node (ref "Slot1") (pin "199") (pintype "input"))
      (node (ref "Slot1") (pin "201") (pintype "input"))
    )
    (net (code "201") (name "VTTREF") (class "Default")
      (node (ref "C85") (pin "2") (pinfunction "2_2") (pintype "passive"))
      (node (ref "C86") (pin "2") (pinfunction "2_2") (pintype "passive"))
      (node (ref "U1") (pin "H6") (pinfunction "PS_DDR_VREF0_502_H6") (pintype "input"))
      (node (ref "U1") (pin "P6") (pinfunction "PS_DDR_VREF1_502_P6") (pintype "input"))
    )
    (net (code "202") (name "unconnected-(Slot1-Pad14)") (class "Default")
      (node (ref "Slot1") (pin "14") (pintype "input+no_connect"))
    )
    (net (code "203") (name "unconnected-(Slot1-Pad16)") (class "Default")
      (node (ref "Slot1") (pin "16") (pintype "input+no_connect"))
    )
    (net (code "204") (name "unconnected-(Slot1-Pad18)") (class "Default")
      (node (ref "Slot1") (pin "18") (pintype "input+no_connect"))
    )
    (net (code "205") (name "unconnected-(Slot1-Pad32)") (class "Default")
      (node (ref "Slot1") (pin "32") (pintype "input+no_connect"))
    )
    (net (code "206") (name "unconnected-(Slot1-Pad106)") (class "Default")
      (node (ref "Slot1") (pin "106") (pintype "input"))
    )
    (net (code "207") (name "unconnected-(Slot1-Pad112)") (class "Default")
      (node (ref "Slot1") (pin "112") (pintype "input"))
    )
    (net (code "208") (name "unconnected-(Slot1-Pad118)") (class "Default")
      (node (ref "Slot1") (pin "118") (pintype "input"))
    )
    (net (code "209") (name "unconnected-(Slot1-Pad124)") (class "Default")
      (node (ref "Slot1") (pin "124") (pintype "input"))
    )
    (net (code "210") (name "unconnected-(Slot1-Pad130)") (class "Default")
      (node (ref "Slot1") (pin "130") (pintype "input"))
    )
    (net (code "211") (name "unconnected-(Slot1-Pad136)") (class "Default")
      (node (ref "Slot1") (pin "136") (pintype "input"))
    )
    (net (code "212") (name "unconnected-(Slot1-Pad142)") (class "Default")
      (node (ref "Slot1") (pin "142") (pintype "input"))
    )
    (net (code "213") (name "unconnected-(Slot1-Pad148)") (class "Default")
      (node (ref "Slot1") (pin "148") (pintype "input"))
    )
    (net (code "214") (name "unconnected-(Slot1-Pad154)") (class "Default")
      (node (ref "Slot1") (pin "154") (pintype "input"))
    )
    (net (code "215") (name "unconnected-(Slot1-Pad160)") (class "Default")
      (node (ref "Slot1") (pin "160") (pintype "input"))
    )
    (net (code "216") (name "unconnected-(Slot1-Pad166)") (class "Default")
      (node (ref "Slot1") (pin "166") (pintype "input"))
    )
    (net (code "217") (name "unconnected-(Slot1-Pad168)") (class "Default")
      (node (ref "Slot1") (pin "168") (pintype "input"))
    )
    (net (code "218") (name "unconnected-(Slot1-Pad170)") (class "Default")
      (node (ref "Slot1") (pin "170") (pintype "input"))
    )
    (net (code "219") (name "unconnected-(Slot1-Pad172)") (class "Default")
      (node (ref "Slot1") (pin "172") (pintype "input"))
    )
    (net (code "220") (name "unconnected-(Slot1-Pad174)") (class "Default")
      (node (ref "Slot1") (pin "174") (pintype "input"))
    )
    (net (code "221") (name "unconnected-(Slot1-Pad176)") (class "Default")
      (node (ref "Slot1") (pin "176") (pintype "input"))
    )
    (net (code "222") (name "unconnected-(Slot1-Pad178)") (class "Default")
      (node (ref "Slot1") (pin "178") (pintype "input"))
    )
    (net (code "223") (name "unconnected-(Slot1-Pad180)") (class "Default")
      (node (ref "Slot1") (pin "180") (pintype "input"))
    )
    (net (code "224") (name "unconnected-(Slot1-Pad182)") (class "Default")
      (node (ref "Slot1") (pin "182") (pintype "input"))
    )
    (net (code "225") (name "unconnected-(Slot1-Pad184)") (class "Default")
      (node (ref "Slot1") (pin "184") (pintype "input"))
    )
    (net (code "226") (name "unconnected-(Slot1-Pad186)") (class "Default")
      (node (ref "Slot1") (pin "186") (pintype "input"))
    )
    (net (code "227") (name "unconnected-(Slot1-Pad198)") (class "Default")
      (node (ref "Slot1") (pin "198") (pintype "input+no_connect"))
    )
    (net (code "228") (name "unconnected-(Slot1-Pad203)") (class "Default")
      (node (ref "Slot1") (pin "203") (pintype "input+no_connect"))
    )
    (net (code "229") (name "unconnected-(U1E-PS_DDR_DM2_502-PadT1)") (class "Default")
      (node (ref "U1") (pin "T1") (pinfunction "PS_DDR_DM2_502_T1") (pintype "output+no_connect"))
    )
    (net (code "230") (name "unconnected-(U1E-PS_DDR_DM3_502-PadY1)") (class "Default")
      (node (ref "U1") (pin "Y1") (pinfunction "PS_DDR_DM3_502_Y1") (pintype "output+no_connect"))
    )
    (net (code "231") (name "unconnected-(U1E-PS_DDR_DQ16_502-PadP1)") (class "Default")
      (node (ref "U1") (pin "P1") (pinfunction "PS_DDR_DQ16_502_P1") (pintype "bidirectional+no_connect"))
    )
    (net (code "232") (name "unconnected-(U1E-PS_DDR_DQ17_502-PadP3)") (class "Default")
      (node (ref "U1") (pin "P3") (pinfunction "PS_DDR_DQ17_502_P3") (pintype "bidirectional+no_connect"))
    )
    (net (code "233") (name "unconnected-(U1E-PS_DDR_DQ18_502-PadR3)") (class "Default")
      (node (ref "U1") (pin "R3") (pinfunction "PS_DDR_DQ18_502_R3") (pintype "bidirectional+no_connect"))
    )
    (net (code "234") (name "unconnected-(U1E-PS_DDR_DQ19_502-PadR1)") (class "Default")
      (node (ref "U1") (pin "R1") (pinfunction "PS_DDR_DQ19_502_R1") (pintype "bidirectional+no_connect"))
    )
    (net (code "235") (name "unconnected-(U1E-PS_DDR_DQ20_502-PadT4)") (class "Default")
      (node (ref "U1") (pin "T4") (pinfunction "PS_DDR_DQ20_502_T4") (pintype "bidirectional+no_connect"))
    )
    (net (code "236") (name "unconnected-(U1E-PS_DDR_DQ21_502-PadU4)") (class "Default")
      (node (ref "U1") (pin "U4") (pinfunction "PS_DDR_DQ21_502_U4") (pintype "bidirectional+no_connect"))
    )
    (net (code "237") (name "unconnected-(U1E-PS_DDR_DQ22_502-PadU2)") (class "Default")
      (node (ref "U1") (pin "U2") (pinfunction "PS_DDR_DQ22_502_U2") (pintype "bidirectional+no_connect"))
    )
    (net (code "238") (name "unconnected-(U1E-PS_DDR_DQ23_502-PadU3)") (class "Default")
      (node (ref "U1") (pin "U3") (pinfunction "PS_DDR_DQ23_502_U3") (pintype "bidirectional+no_connect"))
    )
    (net (code "239") (name "unconnected-(U1E-PS_DDR_DQ24_502-PadV1)") (class "Default")
      (node (ref "U1") (pin "V1") (pinfunction "PS_DDR_DQ24_502_V1") (pintype "bidirectional+no_connect"))
    )
    (net (code "240") (name "unconnected-(U1E-PS_DDR_DQ25_502-PadY3)") (class "Default")
      (node (ref "U1") (pin "Y3") (pinfunction "PS_DDR_DQ25_502_Y3") (pintype "bidirectional+no_connect"))
    )
    (net (code "241") (name "unconnected-(U1E-PS_DDR_DQ26_502-PadW1)") (class "Default")
      (node (ref "U1") (pin "W1") (pinfunction "PS_DDR_DQ26_502_W1") (pintype "bidirectional+no_connect"))
    )
    (net (code "242") (name "unconnected-(U1E-PS_DDR_DQ27_502-PadY4)") (class "Default")
      (node (ref "U1") (pin "Y4") (pinfunction "PS_DDR_DQ27_502_Y4") (pintype "bidirectional+no_connect"))
    )
    (net (code "243") (name "unconnected-(U1E-PS_DDR_DQ28_502-PadY2)") (class "Default")
      (node (ref "U1") (pin "Y2") (pinfunction "PS_DDR_DQ28_502_Y2") (pintype "bidirectional+no_connect"))
    )
    (net (code "244") (name "unconnected-(U1E-PS_DDR_DQ29_502-PadW3)") (class "Default")
      (node (ref "U1") (pin "W3") (pinfunction "PS_DDR_DQ29_502_W3") (pintype "bidirectional+no_connect"))
    )
    (net (code "245") (name "unconnected-(U1E-PS_DDR_DQ30_502-PadV2)") (class "Default")
      (node (ref "U1") (pin "V2") (pinfunction "PS_DDR_DQ30_502_V2") (pintype "bidirectional+no_connect"))
    )
    (net (code "246") (name "unconnected-(U1E-PS_DDR_DQ31_502-PadV3)") (class "Default")
      (node (ref "U1") (pin "V3") (pinfunction "PS_DDR_DQ31_502_V3") (pintype "bidirectional+no_connect"))
    )
    (net (code "247") (name "unconnected-(U1E-PS_DDR_DQS_N2_502-PadT2)") (class "Default")
      (node (ref "U1") (pin "T2") (pinfunction "PS_DDR_DQS_N2_502_T2") (pintype "bidirectional+no_connect"))
    )
    (net (code "248") (name "unconnected-(U1E-PS_DDR_DQS_N3_502-PadW4)") (class "Default")
      (node (ref "U1") (pin "W4") (pinfunction "PS_DDR_DQS_N3_502_W4") (pintype "bidirectional+no_connect"))
    )
    (net (code "249") (name "unconnected-(U1E-PS_DDR_DQS_P2_502-PadR2)") (class "Default")
      (node (ref "U1") (pin "R2") (pinfunction "PS_DDR_DQS_P2_502_R2") (pintype "bidirectional+no_connect"))
    )
    (net (code "250") (name "unconnected-(U1E-PS_DDR_DQS_P3_502-PadW5)") (class "Default")
      (node (ref "U1") (pin "W5") (pinfunction "PS_DDR_DQS_P3_502_W5") (pintype "bidirectional+no_connect"))
    )
    (net (code "251") (name "unconnected-(U1E-PS_DDR_VRN_502-PadG5)") (class "Default")
      (node (ref "U1") (pin "G5") (pinfunction "PS_DDR_VRN_502_G5") (pintype "output+no_connect"))
    )
    (net (code "252") (name "unconnected-(U1E-PS_DDR_VRP_502-PadH5)") (class "Default")
      (node (ref "U1") (pin "H5") (pinfunction "PS_DDR_VRP_502_H5") (pintype "output+no_connect"))
    )
  )
)
